# DMP_SEM_SDCARD.net
KiCad netlist of a schematic drawn in Altium Designer
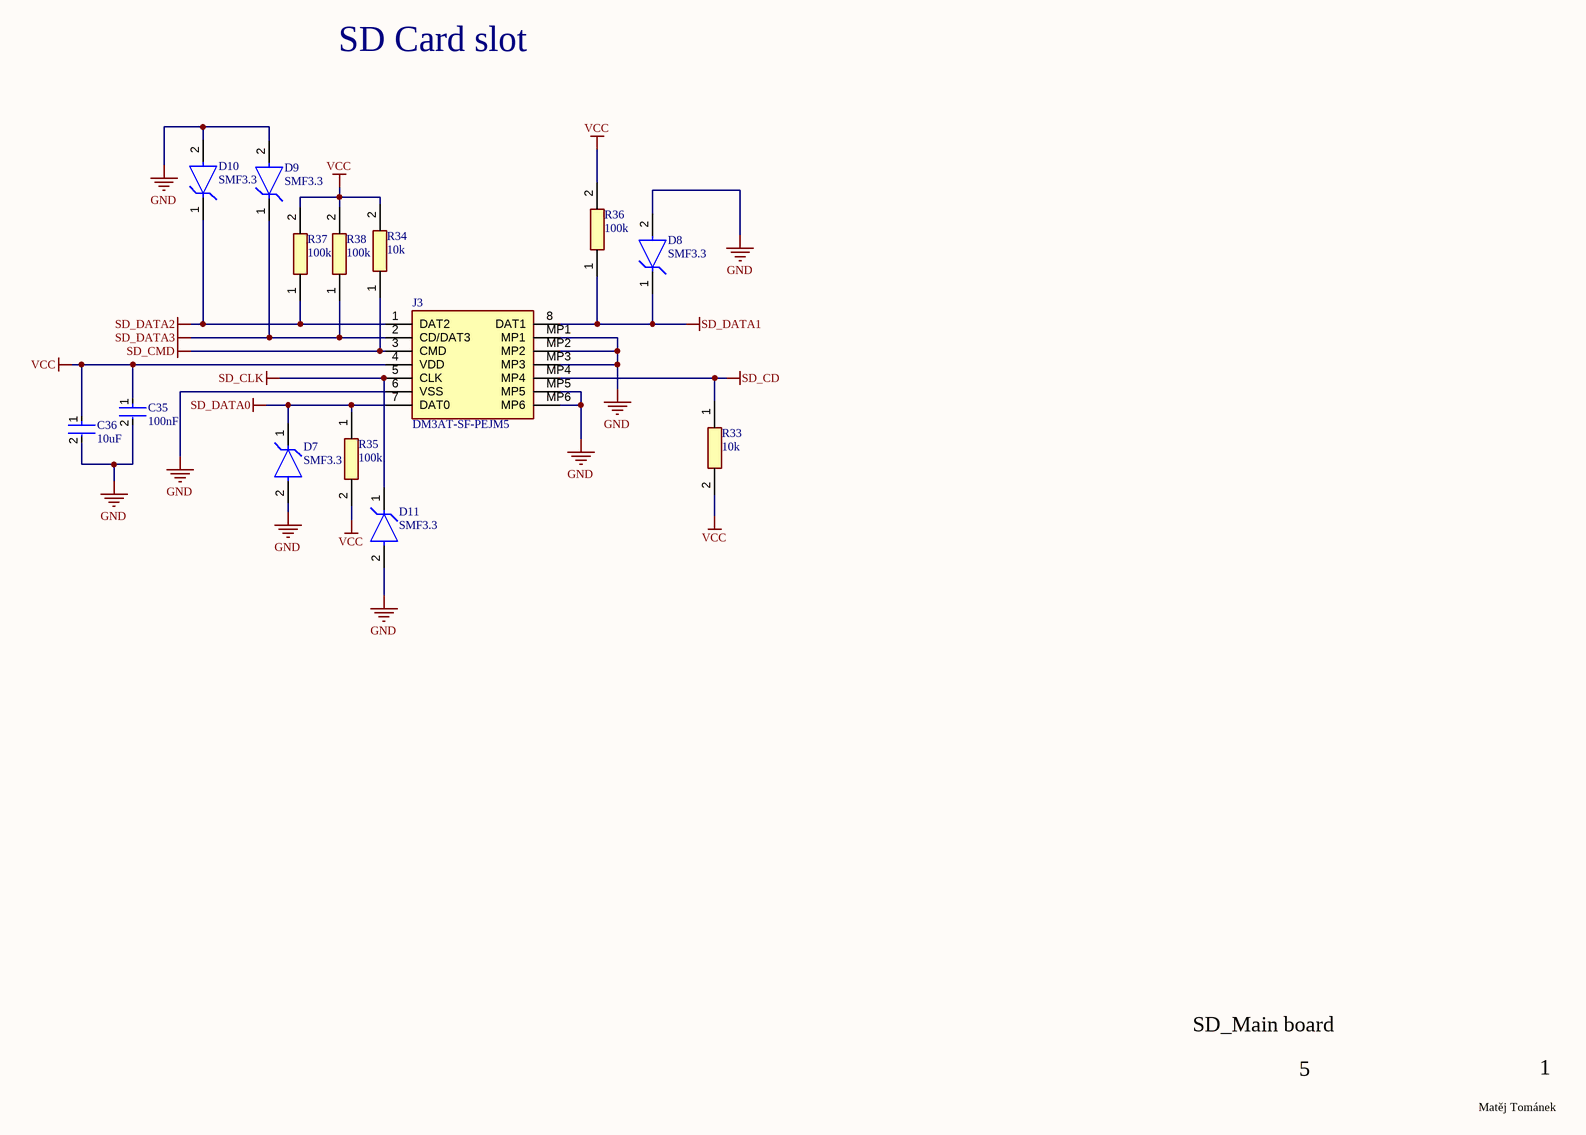
[diagram p0: DMP_SEM_SDCARD.SchDoc]

(export (version "E")
  (design (tool "Eeschema 10.0.6"))
  (components
    (comp (ref "C35")
      (value "100nF")
      (footprint "CL05B104KO5NNNC")
      (description "Capacitor CL05B104KO5NNNC")
      (libsource (lib "DMP_Schlib_SEM_MAIN_BOARD") (part "CL05B104KO5NNNC"))
    )
    (comp (ref "C36")
      (value "10uF")
      (footprint "CL10A106KO8NQNC")
      (description "Capacitor CL10A106KO8NQNC")
      (libsource (lib "DMP_Schlib_SEM_MAIN_BOARD") (part "CL10A106KO8NQNC"))
    )
    (comp (ref "D7")
      (value "SMF3.3")
      (footprint "SMF3.3")
      (description "TVS diode SMF3.3")
      (libsource (lib "DMP_Schlib_SEM_MAIN_BOARD") (part "SMF3.3"))
    )
    (comp (ref "D8")
      (value "SMF3.3")
      (footprint "SMF3.3")
      (description "TVS diode SMF3.3")
      (libsource (lib "DMP_Schlib_SEM_MAIN_BOARD") (part "SMF3.3"))
    )
    (comp (ref "D9")
      (value "SMF3.3")
      (footprint "SMF3.3")
      (description "TVS diode SMF3.3")
      (libsource (lib "DMP_Schlib_SEM_MAIN_BOARD") (part "SMF3.3"))
    )
    (comp (ref "D10")
      (value "SMF3.3")
      (footprint "SMF3.3")
      (description "TVS diode SMF3.3")
      (libsource (lib "DMP_Schlib_SEM_MAIN_BOARD") (part "SMF3.3"))
    )
    (comp (ref "D11")
      (value "SMF3.3")
      (footprint "SMF3.3")
      (description "TVS diode SMF3.3")
      (libsource (lib "DMP_Schlib_SEM_MAIN_BOARD") (part "SMF3.3"))
    )
    (comp (ref "J3")
      (value "DM3AT-SF-PEJM5")
      (footprint "SamacSys:DM3ATSFPEJM5")
      (description "Connector")
      (fields (field (name "MOUSER PART NUMBER") "798-DM3AT-SF-PEJM5"))
      (libsource (lib "*") (part "DM3AT-SF-PEJM5"))
    )
    (comp (ref "R33")
      (value "10k")
      (footprint "CRCW060310K0FKEA")
      (description "Resistor CRCW060310K0FKEA")
      (libsource (lib "DMP_Schlib_SEM_MAIN_BOARD") (part "CRCW060310K0FKEA"))
    )
    (comp (ref "R34")
      (value "10k")
      (footprint "CRCW060310K0FKEA")
      (description "Resistor CRCW060310K0FKEA")
      (libsource (lib "") (part "CRCW060310K0FKEA_1"))
    )
    (comp (ref "R35")
      (value "100k")
      (footprint "ERJ-2RKF1003X")
      (description "Resistor")
      (libsource (lib "") (part "ERJ-2RKF1003X_1"))
    )
    (comp (ref "R36")
      (value "100k")
      (footprint "ERJ-2RKF1003X")
      (description "Resistor")
      (libsource (lib "DMP_Schlib_SEM_MAIN_BOARD") (part "ERJ-2RKF1003X"))
    )
    (comp (ref "R37")
      (value "100k")
      (footprint "ERJ-2RKF1003X")
      (description "Resistor")
      (libsource (lib "DMP_Schlib_SEM_MAIN_BOARD") (part "ERJ-2RKF1003X"))
    )
    (comp (ref "R38")
      (value "100k")
      (footprint "ERJ-2RKF1003X")
      (description "Resistor")
      (libsource (lib "DMP_Schlib_SEM_MAIN_BOARD") (part "ERJ-2RKF1003X"))
    )
  )
  (nets
    (net (code "1") (name "GND") (class "Default")
      (node (ref "C35") (pin "2") (pinfunction "2_2") (pintype "passive"))
      (node (ref "C36") (pin "2") (pinfunction "2_2") (pintype "passive"))
      (node (ref "D10") (pin "2") (pinfunction "A_2") (pintype "passive"))
      (node (ref "D11") (pin "2") (pinfunction "A_2") (pintype "passive"))
      (node (ref "D7") (pin "2") (pinfunction "A_2") (pintype "passive"))
      (node (ref "D8") (pin "2") (pinfunction "A_2") (pintype "passive"))
      (node (ref "D9") (pin "2") (pinfunction "A_2") (pintype "passive"))
      (node (ref "J3") (pin "6") (pinfunction "VSS_6") (pintype "passive"))
      (node (ref "J3") (pin "MP1") (pinfunction "MP1_MP1") (pintype "passive"))
      (node (ref "J3") (pin "MP2") (pinfunction "MP2_MP2") (pintype "passive"))
      (node (ref "J3") (pin "MP3") (pinfunction "MP3_MP3") (pintype "passive"))
      (node (ref "J3") (pin "MP5") (pinfunction "MP5_MP5") (pintype "passive"))
      (node (ref "J3") (pin "MP6") (pinfunction "MP6_MP6") (pintype "passive"))
    )
    (net (code "2") (name "SD_CD") (class "Default")
      (node (ref "J3") (pin "MP4") (pinfunction "MP4_MP4") (pintype "passive"))
      (node (ref "R33") (pin "1") (pinfunction "1_1") (pintype "passive"))
    )
    (net (code "3") (name "SD_CLK") (class "Default")
      (node (ref "D11") (pin "1") (pinfunction "C_1") (pintype "passive"))
      (node (ref "J3") (pin "5") (pinfunction "CLK_5") (pintype "passive"))
    )
    (net (code "4") (name "SD_CMD") (class "Default")
      (node (ref "J3") (pin "3") (pinfunction "CMD_3") (pintype "passive"))
      (node (ref "R34") (pin "1") (pinfunction "1_1") (pintype "passive"))
    )
    (net (code "5") (name "SD_DATA0") (class "Default")
      (node (ref "D7") (pin "1") (pinfunction "C_1") (pintype "passive"))
      (node (ref "J3") (pin "7") (pinfunction "DAT0_7") (pintype "passive"))
      (node (ref "R35") (pin "1") (pinfunction "1_1") (pintype "passive"))
    )
    (net (code "6") (name "SD_DATA1") (class "Default")
      (node (ref "D8") (pin "1") (pinfunction "C_1") (pintype "passive"))
      (node (ref "J3") (pin "8") (pinfunction "DAT1_8") (pintype "passive"))
      (node (ref "R36") (pin "1") (pinfunction "1_1") (pintype "passive"))
    )
    (net (code "7") (name "SD_DATA2") (class "Default")
      (node (ref "D10") (pin "1") (pinfunction "C_1") (pintype "passive"))
      (node (ref "J3") (pin "1") (pinfunction "DAT2_1") (pintype "passive"))
      (node (ref "R37") (pin "1") (pinfunction "1_1") (pintype "passive"))
    )
    (net (code "8") (name "SD_DATA3") (class "Default")
      (node (ref "D9") (pin "1") (pinfunction "C_1") (pintype "passive"))
      (node (ref "J3") (pin "2") (pinfunction "CD/DAT3_2") (pintype "passive"))
      (node (ref "R38") (pin "1") (pinfunction "1_1") (pintype "passive"))
    )
    (net (code "9") (name "VCC") (class "Default")
      (node (ref "C35") (pin "1") (pinfunction "1_1") (pintype "passive"))
      (node (ref "C36") (pin "1") (pinfunction "1_1") (pintype "passive"))
      (node (ref "J3") (pin "4") (pinfunction "VDD_4") (pintype "passive"))
      (node (ref "R33") (pin "2") (pinfunction "2_2") (pintype "passive"))
      (node (ref "R34") (pin "2") (pinfunction "2_2") (pintype "passive"))
      (node (ref "R35") (pin "2") (pinfunction "2_2") (pintype "passive"))
      (node (ref "R36") (pin "2") (pinfunction "2_2") (pintype "passive"))
      (node (ref "R37") (pin "2") (pinfunction "2_2") (pintype "passive"))
      (node (ref "R38") (pin "2") (pinfunction "2_2") (pintype "passive"))
    )
  )
)
